# PDN_Analyzer.net
KiCad netlist of a schematic drawn in Altium Designer
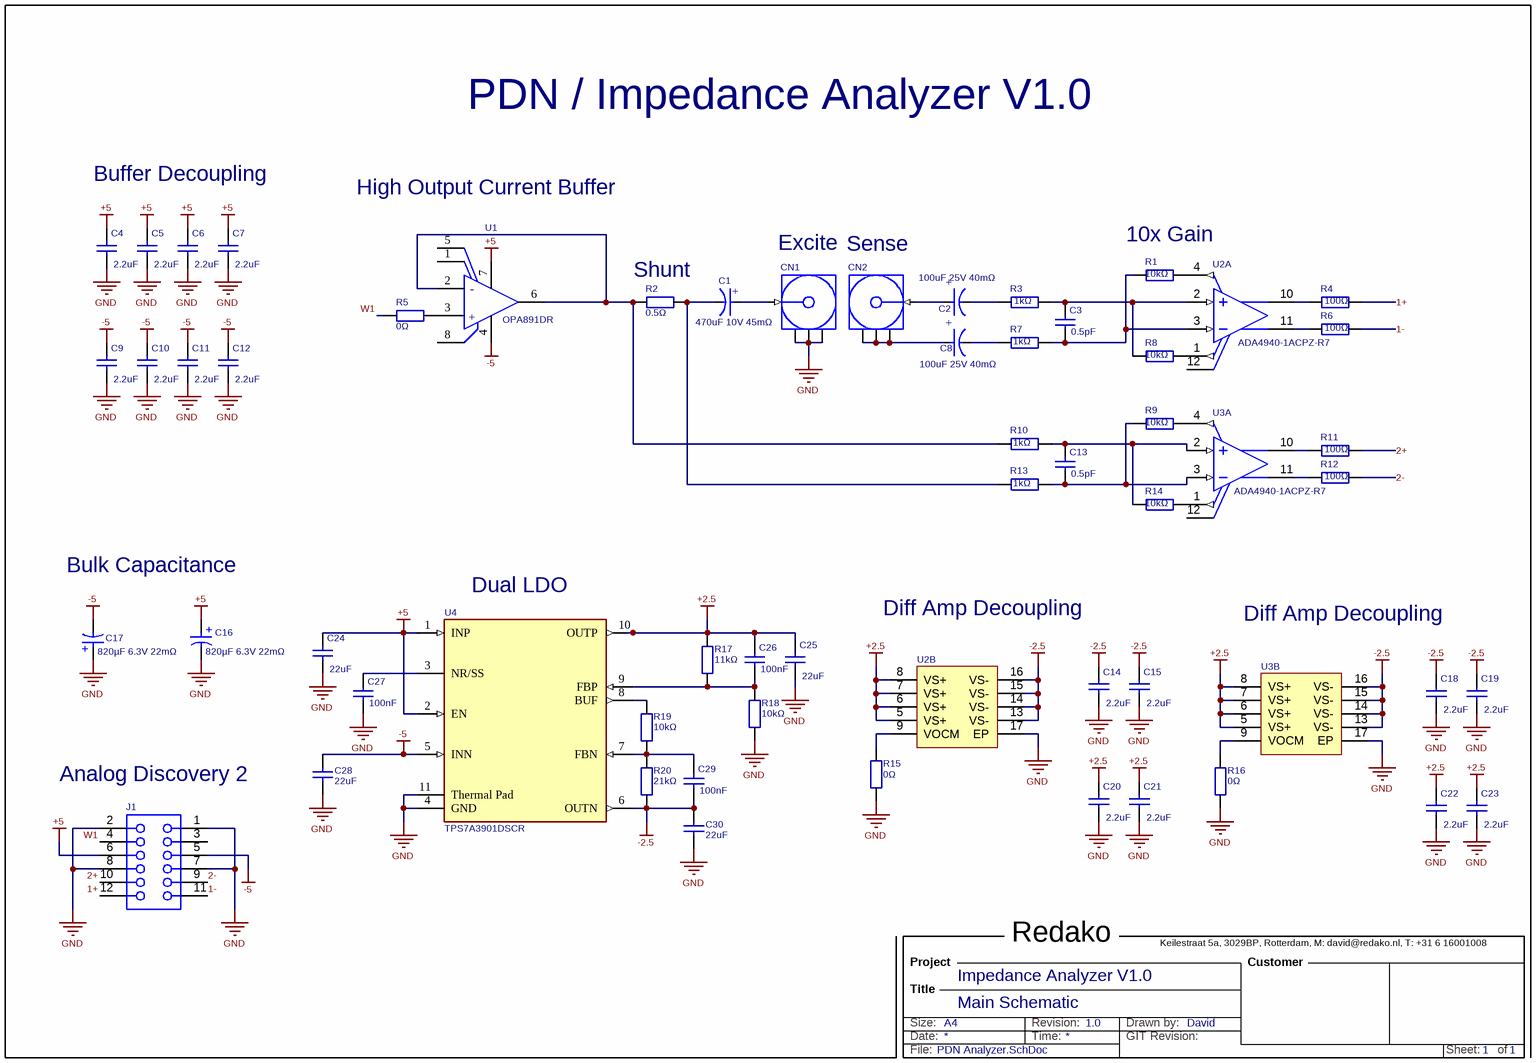
[diagram p0: PDN Analyzer.SchDoc]

(export (version "E")
  (design (tool "Eeschema 10.0.6"))
  (components
    (comp (ref "C1")
      (value "470uF 10V 45mΩ")
      (footprint "FP-T491X107K025AT-MFG")
      (description "CAP TANT 100UF 10% 25V 2917")
      (fields (field (name "Comment") "C4944894"))
      (libsource (lib "Altium Content Vault") (part "cf48714ba7e38822c1575c7ec0b6d1f"))
    )
    (comp (ref "C2")
      (value "100uF 25V 40mΩ")
      (footprint "FP-T521X-MFG")
      (description "CAP TANT POLY 100UF 25V 2917")
      (fields (field (name "Comment") "C696814"))
      (libsource (lib "Altium Content Vault") (part "cf48714ba7e38822c1575c7ec0b6d1f"))
    )
    (comp (ref "C3")
      (value "0.5pF")
      (footprint "CAPC1005X05N")
      (libsource (lib "SchematicLibrary") (part "SMD_Cap"))
    )
    (comp (ref "C4")
      (value "2.2uF")
      (footprint "CAPC1005X05N")
      (libsource (lib "SchematicLibrary") (part "SMD_Cap"))
    )
    (comp (ref "C5")
      (value "2.2uF")
      (footprint "CAPC1005X05N")
      (libsource (lib "SchematicLibrary") (part "SMD_Cap"))
    )
    (comp (ref "C6")
      (value "2.2uF")
      (footprint "CAPC1005X05N")
      (libsource (lib "SchematicLibrary") (part "SMD_Cap"))
    )
    (comp (ref "C7")
      (value "2.2uF")
      (footprint "CAPC1005X05N")
      (libsource (lib "SchematicLibrary") (part "SMD_Cap"))
    )
    (comp (ref "C8")
      (value "100uF 25V 40mΩ")
      (footprint "FP-T521X-MFG")
      (description "CAP TANT POLY 100UF 25V 2917")
      (fields (field (name "Comment") "C696814"))
      (libsource (lib "Altium Content Vault") (part "cf48714ba7e38822c1575c7ec0b6d1f"))
    )
    (comp (ref "C9")
      (value "2.2uF")
      (footprint "CAPC1005X05N")
      (libsource (lib "SchematicLibrary") (part "SMD_Cap"))
    )
    (comp (ref "C10")
      (value "2.2uF")
      (footprint "CAPC1005X05N")
      (libsource (lib "SchematicLibrary") (part "SMD_Cap"))
    )
    (comp (ref "C11")
      (value "2.2uF")
      (footprint "CAPC1005X05N")
      (libsource (lib "SchematicLibrary") (part "SMD_Cap"))
    )
    (comp (ref "C12")
      (value "2.2uF")
      (footprint "CAPC1005X05N")
      (libsource (lib "SchematicLibrary") (part "SMD_Cap"))
    )
    (comp (ref "C13")
      (value "0.5pF")
      (footprint "CAPC1005X05N")
      (libsource (lib "SchematicLibrary") (part "SMD_Cap"))
    )
    (comp (ref "C14")
      (value "2.2uF")
      (footprint "CAPC1005X05N")
      (libsource (lib "SchematicLibrary") (part "SMD_Cap"))
    )
    (comp (ref "C15")
      (value "2.2uF")
      (footprint "CAPC1005X05N")
      (libsource (lib "SchematicLibrary") (part "SMD_Cap"))
    )
    (comp (ref "C16")
      (value "820µF 6.3V 22mΩ")
      (footprint "WCAP-PSLP_D6.3H5.8")
      (description "875105144008 WCAP-PSLP Aluminum Polymer Capacitors")
      (fields (field (name "MPN") "HV0J827M0607PZ") (field (name "Comment") "C5246508"))
      (libsource (lib "Altium Content Vault") (part "Capacitor_Polarized"))
    )
    (comp (ref "C17")
      (value "820µF 6.3V 22mΩ")
      (footprint "WCAP-PSLP_D6.3H5.8")
      (description "875105144008 WCAP-PSLP Aluminum Polymer Capacitors")
      (fields (field (name "MPN") "HV0J827M0607PZ") (field (name "Comment") "C5246508"))
      (libsource (lib "Altium Content Vault") (part "Capacitor_Polarized"))
    )
    (comp (ref "C18")
      (value "2.2uF")
      (footprint "CAPC1005X05N")
      (libsource (lib "SchematicLibrary") (part "SMD_Cap"))
    )
    (comp (ref "C19")
      (value "2.2uF")
      (footprint "CAPC1005X05N")
      (libsource (lib "SchematicLibrary") (part "SMD_Cap"))
    )
    (comp (ref "C20")
      (value "2.2uF")
      (footprint "CAPC1005X05N")
      (libsource (lib "SchematicLibrary") (part "SMD_Cap"))
    )
    (comp (ref "C21")
      (value "2.2uF")
      (footprint "CAPC1005X05N")
      (libsource (lib "SchematicLibrary") (part "SMD_Cap"))
    )
    (comp (ref "C22")
      (value "2.2uF")
      (footprint "CAPC1005X05N")
      (libsource (lib "SchematicLibrary") (part "SMD_Cap"))
    )
    (comp (ref "C23")
      (value "2.2uF")
      (footprint "CAPC1005X05N")
      (libsource (lib "SchematicLibrary") (part "SMD_Cap"))
    )
    (comp (ref "C24")
      (value "22uF")
      (footprint "CAPC1005X05N")
      (libsource (lib "SchematicLibrary") (part "SMD_Cap"))
    )
    (comp (ref "C25")
      (value "22uF")
      (footprint "CAPC1005X05N")
      (libsource (lib "SchematicLibrary") (part "SMD_Cap"))
    )
    (comp (ref "C26")
      (value "100nF")
      (footprint "CAPC1005X05N")
      (libsource (lib "SchematicLibrary") (part "SMD_Cap"))
    )
    (comp (ref "C27")
      (value "100nF")
      (footprint "CAPC1005X05N")
      (libsource (lib "SchematicLibrary") (part "SMD_Cap"))
    )
    (comp (ref "C28")
      (value "22uF")
      (footprint "CAPC1005X05N")
      (libsource (lib "SchematicLibrary") (part "SMD_Cap"))
    )
    (comp (ref "C29")
      (value "100nF")
      (footprint "CAPC1005X05N")
      (libsource (lib "SchematicLibrary") (part "SMD_Cap"))
    )
    (comp (ref "C30")
      (value "22uF")
      (footprint "CAPC1005X05N")
      (libsource (lib "SchematicLibrary") (part "SMD_Cap"))
    )
    (comp (ref "CN1")
      (value "C434806")
      (footprint "MOLX-73412-0110_V")
      (description "MCRF, PCB Vertical Jack Receptacle, 50 Ohm, 4-Pin SMD, RoHS, Tape and Reel")
      (fields (field (name "MPN") "73412-0110") (field (name "MANUFACTURER") "Molex"))
      (libsource (lib "Altium Content Vault") (part "MOLX-73412-0110"))
    )
    (comp (ref "CN2")
      (value "C434806")
      (footprint "MOLX-73412-0110_V")
      (description "MCRF, PCB Vertical Jack Receptacle, 50 Ohm, 4-Pin SMD, RoHS, Tape and Reel")
      (fields (field (name "MPN") "73412-0110") (field (name "MANUFACTURER") "Molex"))
      (libsource (lib "Altium Content Vault") (part "MOLX-73412-0110"))
    )
    (comp (ref "J1")
      (value "C5333437")
      (footprint "613012243121")
      (fields (field (name "MPN") "A2541HWR-2x6P"))
      (libsource (lib "Altium Content Vault") (part "Header_Female_2R_12P"))
    )
    (comp (ref "R1")
      (value "10kΩ")
      (footprint "RESC1005X04N")
      (libsource (lib "SchematicLibrary") (part "Res"))
    )
    (comp (ref "R2")
      (value "0.5Ω")
      (footprint "RESC1608X04N")
      (libsource (lib "SchematicLibrary") (part "Res"))
    )
    (comp (ref "R3")
      (value "1kΩ")
      (footprint "RESC1005X04N")
      (libsource (lib "SchematicLibrary") (part "Res"))
    )
    (comp (ref "R4")
      (value "100Ω")
      (footprint "RESC1005X04N")
      (libsource (lib "SchematicLibrary") (part "Res"))
    )
    (comp (ref "R5")
      (value "0Ω")
      (footprint "RESC1608X04N")
      (libsource (lib "SchematicLibrary") (part "Res"))
    )
    (comp (ref "R6")
      (value "100Ω")
      (footprint "RESC1005X04N")
      (libsource (lib "SchematicLibrary") (part "Res"))
    )
    (comp (ref "R7")
      (value "1kΩ")
      (footprint "RESC1005X04N")
      (libsource (lib "SchematicLibrary") (part "Res"))
    )
    (comp (ref "R8")
      (value "10kΩ")
      (footprint "RESC1005X04N")
      (libsource (lib "SchematicLibrary") (part "Res"))
    )
    (comp (ref "R9")
      (value "10kΩ")
      (footprint "RESC1005X04N")
      (libsource (lib "SchematicLibrary") (part "Res"))
    )
    (comp (ref "R10")
      (value "1kΩ")
      (footprint "RESC1005X04N")
      (libsource (lib "SchematicLibrary") (part "Res"))
    )
    (comp (ref "R11")
      (value "100Ω")
      (footprint "RESC1005X04N")
      (libsource (lib "SchematicLibrary") (part "Res"))
    )
    (comp (ref "R12")
      (value "100Ω")
      (footprint "RESC1005X04N")
      (libsource (lib "SchematicLibrary") (part "Res"))
    )
    (comp (ref "R13")
      (value "1kΩ")
      (footprint "RESC1005X04N")
      (libsource (lib "SchematicLibrary") (part "Res"))
    )
    (comp (ref "R14")
      (value "10kΩ")
      (footprint "RESC1005X04N")
      (libsource (lib "SchematicLibrary") (part "Res"))
    )
    (comp (ref "R15")
      (value "0Ω")
      (footprint "RESC1005X04N")
      (libsource (lib "SchematicLibrary") (part "Res"))
    )
    (comp (ref "R16")
      (value "0Ω")
      (footprint "RESC1005X04N")
      (libsource (lib "SchematicLibrary") (part "Res"))
    )
    (comp (ref "R17")
      (value "11kΩ")
      (footprint "RESC1005X04N")
      (libsource (lib "SchematicLibrary") (part "Res"))
    )
    (comp (ref "R18")
      (value "10kΩ")
      (footprint "RESC1005X04N")
      (libsource (lib "SchematicLibrary") (part "Res"))
    )
    (comp (ref "R19")
      (value "10kΩ")
      (footprint "RESC1005X04N")
      (libsource (lib "SchematicLibrary") (part "Res"))
    )
    (comp (ref "R20")
      (value "21kΩ")
      (footprint "RESC1005X04N")
      (libsource (lib "SchematicLibrary") (part "Res"))
    )
    (comp (ref "U1")
      (value "C22444686")
      (footprint "FP-D0008A-MFG")
      (fields (field (name "MANUFACTURER") "Texas Instruments") (field (name "MPN") "OPA891DR"))
      (libsource (lib "Altium Content Vault") (part "6d921cdaf6a95fe38fdc69a31941bad"))
    )
    (comp (ref "U2")
      (value "C468516")
      (footprint "ADI-CP-16-2_M")
      (fields (field (name "MANUFACTURER") "Analog Devices") (field (name "MPN") "ADA4940-1ACPZ-R7"))
      (libsource (lib "Altium Content Vault") (part "ADI-ADA4940-CP-16-2"))
    )
    (comp (ref "U3")
      (value "C468516")
      (footprint "ADI-CP-16-2_M")
      (fields (field (name "MANUFACTURER") "Analog Devices") (field (name "MPN") "ADA4940-1ACPZ-R7"))
      (libsource (lib "Altium Content Vault") (part "ADI-ADA4940-CP-16-2"))
    )
    (comp (ref "U4")
      (value "TPS7A3901DSCR")
      (footprint "FP-DSC0010J-MFG")
      (description "IC REG LINEAR POS/NEG ADJ 10WSON")
      (libsource (lib "Altium Content Vault") (part "72cd728b6036b03d48b600323a815d5"))
    )
  )
  (nets
    (net (code "1") (name "+2.5") (class "Default")
      (node (ref "C20") (pin "2") (pintype "passive"))
      (node (ref "C21") (pin "2") (pintype "passive"))
      (node (ref "C22") (pin "2") (pintype "passive"))
      (node (ref "C23") (pin "2") (pintype "passive"))
      (node (ref "C25") (pin "2") (pintype "passive"))
      (node (ref "C26") (pin "2") (pintype "passive"))
      (node (ref "R17") (pin "2") (pintype "passive"))
      (node (ref "U2") (pin "5") (pinfunction "VS+_5") (pintype "power_in"))
      (node (ref "U2") (pin "6") (pinfunction "VS+_6") (pintype "power_in"))
      (node (ref "U2") (pin "7") (pinfunction "VS+_7") (pintype "power_in"))
      (node (ref "U2") (pin "8") (pinfunction "VS+_8") (pintype "power_in"))
      (node (ref "U3") (pin "5") (pinfunction "VS+_5") (pintype "power_in"))
      (node (ref "U3") (pin "6") (pinfunction "VS+_6") (pintype "power_in"))
      (node (ref "U3") (pin "7") (pinfunction "VS+_7") (pintype "power_in"))
      (node (ref "U3") (pin "8") (pinfunction "VS+_8") (pintype "power_in"))
      (node (ref "U4") (pin "10") (pinfunction "OUTP_10") (pintype "output"))
    )
    (net (code "2") (name "+5") (class "Default")
      (node (ref "C16") (pin "1") (pinfunction "P_1") (pintype "passive"))
      (node (ref "C24") (pin "2") (pintype "passive"))
      (node (ref "C4") (pin "2") (pintype "passive"))
      (node (ref "C5") (pin "2") (pintype "passive"))
      (node (ref "C6") (pin "2") (pintype "passive"))
      (node (ref "C7") (pin "2") (pintype "passive"))
      (node (ref "J1") (pin "6") (pinfunction "6_6") (pintype "passive"))
      (node (ref "U1") (pin "7") (pinfunction "VCC+_7") (pintype "power_in"))
      (node (ref "U4") (pin "1") (pinfunction "INP_1") (pintype "input"))
      (node (ref "U4") (pin "2") (pinfunction "EN_2") (pintype "input"))
    )
    (net (code "3") (name "-2.5") (class "Default")
      (node (ref "C14") (pin "2") (pintype "passive"))
      (node (ref "C15") (pin "2") (pintype "passive"))
      (node (ref "C18") (pin "2") (pintype "passive"))
      (node (ref "C19") (pin "2") (pintype "passive"))
      (node (ref "C29") (pin "1") (pintype "passive"))
      (node (ref "C30") (pin "1") (pintype "passive"))
      (node (ref "R20") (pin "1") (pintype "passive"))
      (node (ref "U2") (pin "13") (pinfunction "VS-_13") (pintype "power_in"))
      (node (ref "U2") (pin "14") (pinfunction "VS-_14") (pintype "power_in"))
      (node (ref "U2") (pin "15") (pinfunction "VS-_15") (pintype "power_in"))
      (node (ref "U2") (pin "16") (pinfunction "VS-_16") (pintype "power_in"))
      (node (ref "U3") (pin "13") (pinfunction "VS-_13") (pintype "power_in"))
      (node (ref "U3") (pin "14") (pinfunction "VS-_14") (pintype "power_in"))
      (node (ref "U3") (pin "15") (pinfunction "VS-_15") (pintype "power_in"))
      (node (ref "U3") (pin "16") (pinfunction "VS-_16") (pintype "power_in"))
      (node (ref "U4") (pin "6") (pinfunction "OUTN_6") (pintype "output"))
    )
    (net (code "4") (name "-5") (class "Default")
      (node (ref "C10") (pin "2") (pintype "passive"))
      (node (ref "C11") (pin "2") (pintype "passive"))
      (node (ref "C12") (pin "2") (pintype "passive"))
      (node (ref "C17") (pin "2") (pinfunction "N_2") (pintype "passive"))
      (node (ref "C28") (pin "1") (pintype "passive"))
      (node (ref "C9") (pin "2") (pintype "passive"))
      (node (ref "J1") (pin "5") (pinfunction "5_5") (pintype "passive"))
      (node (ref "U1") (pin "4") (pinfunction "VCC-_4") (pintype "power_in"))
      (node (ref "U4") (pin "5") (pinfunction "INN_5") (pintype "input"))
    )
    (net (code "5") (name "/1+") (class "Default")
      (node (ref "J1") (pin "12") (pinfunction "12_12") (pintype "passive"))
      (node (ref "R4") (pin "1") (pintype "passive"))
    )
    (net (code "6") (name "/1-") (class "Default")
      (node (ref "J1") (pin "11") (pinfunction "11_11") (pintype "passive"))
      (node (ref "R6") (pin "1") (pintype "passive"))
    )
    (net (code "7") (name "/2+") (class "Default")
      (node (ref "J1") (pin "10") (pinfunction "10_10") (pintype "passive"))
      (node (ref "R11") (pin "1") (pintype "passive"))
    )
    (net (code "8") (name "/2-") (class "Default")
      (node (ref "J1") (pin "9") (pinfunction "9_9") (pintype "passive"))
      (node (ref "R12") (pin "1") (pintype "passive"))
    )
    (net (code "9") (name "/W1") (class "Default")
      (node (ref "J1") (pin "4") (pinfunction "4_4") (pintype "passive"))
      (node (ref "R5") (pin "2") (pintype "passive"))
    )
    (net (code "10") (name "GND") (class "Default")
      (node (ref "C10") (pin "1") (pintype "passive"))
      (node (ref "C11") (pin "1") (pintype "passive"))
      (node (ref "C12") (pin "1") (pintype "passive"))
      (node (ref "C14") (pin "1") (pintype "passive"))
      (node (ref "C15") (pin "1") (pintype "passive"))
      (node (ref "C16") (pin "2") (pinfunction "N_2") (pintype "passive"))
      (node (ref "C17") (pin "1") (pinfunction "P_1") (pintype "passive"))
      (node (ref "C18") (pin "1") (pintype "passive"))
      (node (ref "C19") (pin "1") (pintype "passive"))
      (node (ref "C20") (pin "1") (pintype "passive"))
      (node (ref "C21") (pin "1") (pintype "passive"))
      (node (ref "C22") (pin "1") (pintype "passive"))
      (node (ref "C23") (pin "1") (pintype "passive"))
      (node (ref "C24") (pin "1") (pintype "passive"))
      (node (ref "C25") (pin "1") (pintype "passive"))
      (node (ref "C27") (pin "1") (pintype "passive"))
      (node (ref "C28") (pin "2") (pintype "passive"))
      (node (ref "C30") (pin "2") (pintype "passive"))
      (node (ref "C4") (pin "1") (pintype "passive"))
      (node (ref "C5") (pin "1") (pintype "passive"))
      (node (ref "C6") (pin "1") (pintype "passive"))
      (node (ref "C7") (pin "1") (pintype "passive"))
      (node (ref "C9") (pin "1") (pintype "passive"))
      (node (ref "CN1") (pin "2") (pinfunction "GND_2") (pintype "power_in"))
      (node (ref "CN1") (pin "3") (pinfunction "GND_3") (pintype "power_in"))
      (node (ref "CN1") (pin "4") (pinfunction "GND_4") (pintype "power_in"))
      (node (ref "J1") (pin "1") (pinfunction "1_1") (pintype "passive"))
      (node (ref "J1") (pin "2") (pinfunction "2_2") (pintype "passive"))
      (node (ref "J1") (pin "7") (pinfunction "7_7") (pintype "passive"))
      (node (ref "J1") (pin "8") (pinfunction "8_8") (pintype "passive"))
      (node (ref "R15") (pin "2") (pintype "passive"))
      (node (ref "R16") (pin "2") (pintype "passive"))
      (node (ref "R18") (pin "2") (pintype "passive"))
      (node (ref "U2") (pin "17") (pinfunction "EP_17") (pintype "power_in"))
      (node (ref "U3") (pin "17") (pinfunction "EP_17") (pintype "power_in"))
      (node (ref "U4") (pin "11") (pinfunction "Thermal_Pad_11") (pintype "power_in"))
      (node (ref "U4") (pin "4") (pinfunction "GND_4") (pintype "power_in"))
    )
    (net (code "11") (name "Net-(C1-A)") (class "Default")
      (node (ref "C1") (pin "2") (pinfunction "A_2") (pintype "passive"))
      (node (ref "CN1") (pin "1") (pinfunction "SIGNAL_1") (pintype "input"))
    )
    (net (code "12") (name "Net-(C1-C)") (class "Default")
      (node (ref "C1") (pin "1") (pinfunction "C_1") (pintype "passive"))
      (node (ref "R13") (pin "2") (pintype "passive"))
      (node (ref "R2") (pin "1") (pintype "passive"))
    )
    (net (code "13") (name "Net-(C2-A)") (class "Default")
      (node (ref "C2") (pin "2") (pinfunction "A_2") (pintype "passive"))
      (node (ref "CN2") (pin "1") (pinfunction "SIGNAL_1") (pintype "input"))
    )
    (net (code "14") (name "Net-(C2-C)") (class "Default")
      (node (ref "C2") (pin "1") (pinfunction "C_1") (pintype "passive"))
      (node (ref "R3") (pin "2") (pintype "passive"))
    )
    (net (code "15") (name "Net-(C8-A)") (class "Default")
      (node (ref "C8") (pin "2") (pinfunction "A_2") (pintype "passive"))
      (node (ref "CN2") (pin "2") (pinfunction "GND_2") (pintype "power_in"))
      (node (ref "CN2") (pin "3") (pinfunction "GND_3") (pintype "power_in"))
      (node (ref "CN2") (pin "4") (pinfunction "GND_4") (pintype "power_in"))
    )
    (net (code "16") (name "Net-(C8-C)") (class "Default")
      (node (ref "C8") (pin "1") (pinfunction "C_1") (pintype "passive"))
      (node (ref "R7") (pin "2") (pintype "passive"))
    )
    (net (code "17") (name "Net-(U1-IN+)") (class "Default")
      (node (ref "R5") (pin "1") (pintype "passive"))
      (node (ref "U1") (pin "3") (pinfunction "IN+_3") (pintype "tri_state"))
    )
    (net (code "18") (name "Net-(U1-IN-)") (class "Default")
      (node (ref "R10") (pin "2") (pintype "passive"))
      (node (ref "R2") (pin "2") (pintype "passive"))
      (node (ref "U1") (pin "2") (pinfunction "IN-_2") (pintype "tri_state"))
      (node (ref "U1") (pin "6") (pinfunction "OUT_6") (pintype "passive"))
    )
    (net (code "19") (name "Net-(U2A-FB+)") (class "Default")
      (node (ref "R1") (pin "1") (pintype "passive"))
      (node (ref "U2") (pin "4") (pinfunction "FB+_4") (pintype "output"))
    )
    (net (code "20") (name "Net-(U2A-FB-)") (class "Default")
      (node (ref "R8") (pin "1") (pintype "passive"))
      (node (ref "U2") (pin "1") (pinfunction "FB-_1") (pintype "output"))
    )
    (net (code "21") (name "Net-(U2A-IN+)") (class "Default")
      (node (ref "C3") (pin "2") (pintype "passive"))
      (node (ref "R3") (pin "1") (pintype "passive"))
      (node (ref "R8") (pin "2") (pintype "passive"))
      (node (ref "U2") (pin "2") (pinfunction "IN+_2") (pintype "input"))
    )
    (net (code "22") (name "Net-(U2A-IN-)") (class "Default")
      (node (ref "C3") (pin "1") (pintype "passive"))
      (node (ref "R1") (pin "2") (pintype "passive"))
      (node (ref "R7") (pin "1") (pintype "passive"))
      (node (ref "U2") (pin "3") (pinfunction "IN-_3") (pintype "input"))
    )
    (net (code "23") (name "Net-(U2A-OUT+)") (class "Default")
      (node (ref "R4") (pin "2") (pintype "passive"))
      (node (ref "U2") (pin "10") (pinfunction "OUT+_10") (pintype "tri_state"))
    )
    (net (code "24") (name "Net-(U2A-OUT-)") (class "Default")
      (node (ref "R6") (pin "2") (pintype "passive"))
      (node (ref "U2") (pin "11") (pinfunction "OUT-_11") (pintype "tri_state"))
    )
    (net (code "25") (name "Net-(U2B-VOCM)") (class "Default")
      (node (ref "R15") (pin "1") (pintype "passive"))
      (node (ref "U2") (pin "9") (pinfunction "VOCM_9") (pintype "power_in"))
    )
    (net (code "26") (name "Net-(U3A-FB+)") (class "Default")
      (node (ref "R9") (pin "1") (pintype "passive"))
      (node (ref "U3") (pin "4") (pinfunction "FB+_4") (pintype "output"))
    )
    (net (code "27") (name "Net-(U3A-FB-)") (class "Default")
      (node (ref "R14") (pin "1") (pintype "passive"))
      (node (ref "U3") (pin "1") (pinfunction "FB-_1") (pintype "output"))
    )
    (net (code "28") (name "Net-(U3A-IN+)") (class "Default")
      (node (ref "C13") (pin "2") (pintype "passive"))
      (node (ref "R10") (pin "1") (pintype "passive"))
      (node (ref "R14") (pin "2") (pintype "passive"))
      (node (ref "U3") (pin "2") (pinfunction "IN+_2") (pintype "input"))
    )
    (net (code "29") (name "Net-(U3A-IN-)") (class "Default")
      (node (ref "C13") (pin "1") (pintype "passive"))
      (node (ref "R13") (pin "1") (pintype "passive"))
      (node (ref "R9") (pin "2") (pintype "passive"))
      (node (ref "U3") (pin "3") (pinfunction "IN-_3") (pintype "input"))
    )
    (net (code "30") (name "Net-(U3A-OUT+)") (class "Default")
      (node (ref "R11") (pin "2") (pintype "passive"))
      (node (ref "U3") (pin "10") (pinfunction "OUT+_10") (pintype "tri_state"))
    )
    (net (code "31") (name "Net-(U3A-OUT-)") (class "Default")
      (node (ref "R12") (pin "2") (pintype "passive"))
      (node (ref "U3") (pin "11") (pinfunction "OUT-_11") (pintype "tri_state"))
    )
    (net (code "32") (name "Net-(U3B-VOCM)") (class "Default")
      (node (ref "R16") (pin "1") (pintype "passive"))
      (node (ref "U3") (pin "9") (pinfunction "VOCM_9") (pintype "power_in"))
    )
    (net (code "33") (name "Net-(U4-BUF)") (class "Default")
      (node (ref "R19") (pin "2") (pintype "passive"))
      (node (ref "U4") (pin "8") (pinfunction "BUF_8") (pintype "output"))
    )
    (net (code "34") (name "Net-(U4-FBN)") (class "Default")
      (node (ref "C29") (pin "2") (pintype "passive"))
      (node (ref "R19") (pin "1") (pintype "passive"))
      (node (ref "R20") (pin "2") (pintype "passive"))
      (node (ref "U4") (pin "7") (pinfunction "FBN_7") (pintype "input"))
    )
    (net (code "35") (name "Net-(U4-FBP)") (class "Default")
      (node (ref "C26") (pin "1") (pintype "passive"))
      (node (ref "R17") (pin "1") (pintype "passive"))
      (node (ref "R18") (pin "1") (pintype "passive"))
      (node (ref "U4") (pin "9") (pinfunction "FBP_9") (pintype "input"))
    )
    (net (code "36") (name "Net-(U4-NR{slash}SS)") (class "Default")
      (node (ref "C27") (pin "2") (pintype "passive"))
      (node (ref "U4") (pin "3") (pinfunction "NR/SS_3") (pintype "passive"))
    )
    (net (code "37") (name "unconnected-(J1-Pad3)") (class "Default")
      (node (ref "J1") (pin "3") (pinfunction "3_3") (pintype "passive"))
    )
    (net (code "38") (name "unconnected-(U1-1_NULL-Pad1)") (class "Default")
      (node (ref "U1") (pin "1") (pinfunction "1_NULL_1") (pintype "passive"))
    )
    (net (code "39") (name "unconnected-(U1-2_NULL-Pad8)") (class "Default")
      (node (ref "U1") (pin "8") (pinfunction "2_NULL_8") (pintype "passive"))
    )
    (net (code "40") (name "unconnected-(U1-NC-Pad5)") (class "Default")
      (node (ref "U1") (pin "5") (pinfunction "NC_5") (pintype "passive"))
    )
    (net (code "41") (name "unconnected-(U2A-~{DISABLE}-Pad12)") (class "Default")
      (node (ref "U2") (pin "12") (pinfunction "~{DISABLE}_12") (pintype "passive"))
    )
    (net (code "42") (name "unconnected-(U3A-~{DISABLE}-Pad12)") (class "Default")
      (node (ref "U3") (pin "12") (pinfunction "~{DISABLE}_12") (pintype "passive"))
    )
  )
)
